# aprs_v2.net
KiCad netlist of a schematic drawn in EAGLE
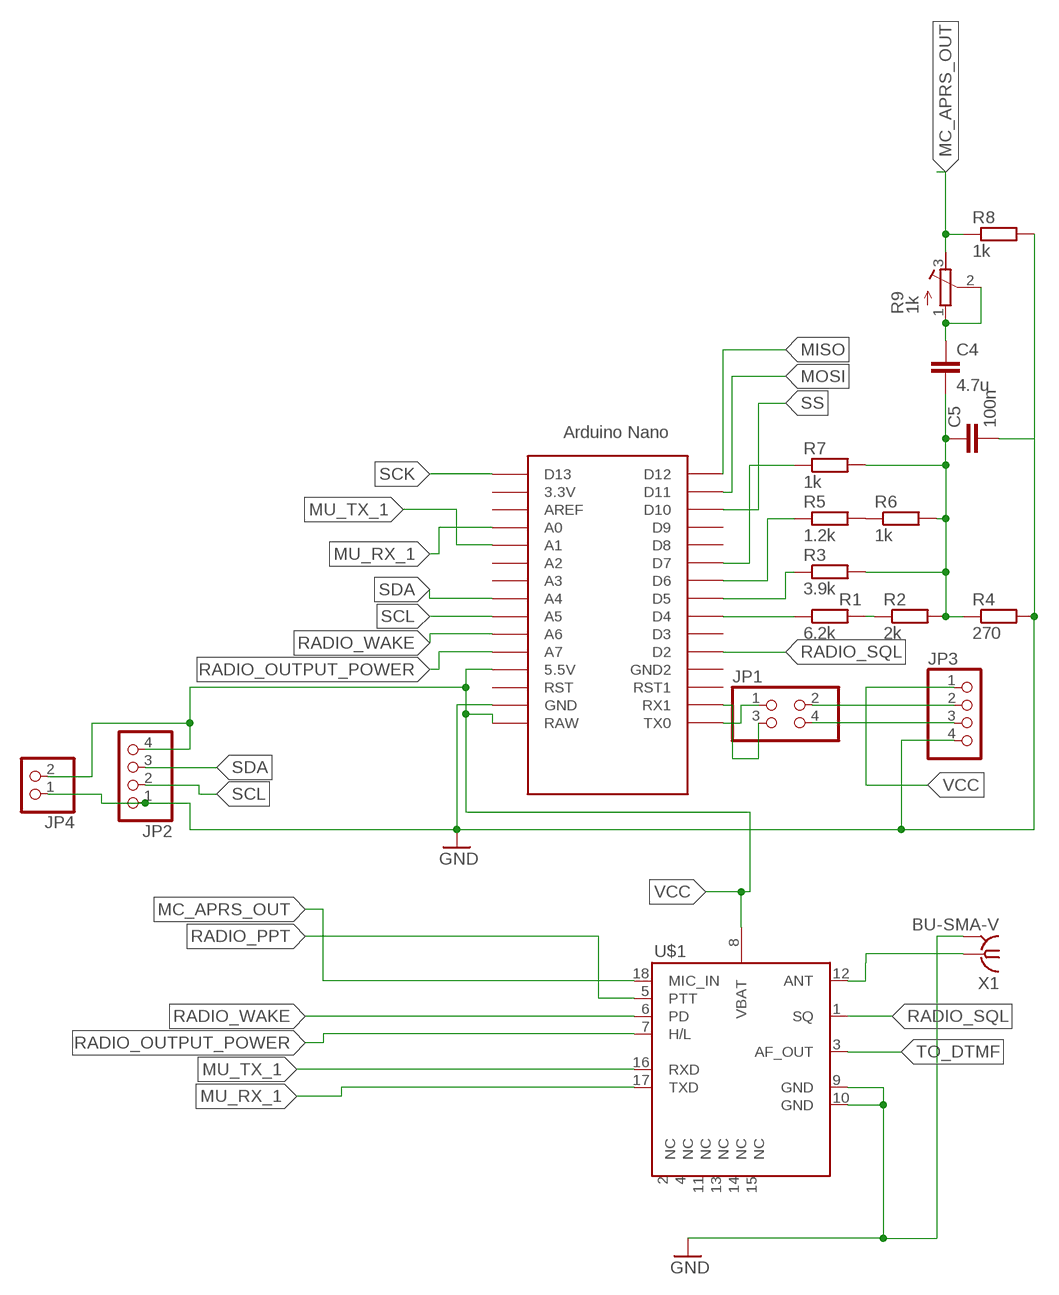
[diagram p0: schematic, sheet 1]

(export (version "E")
  (design (tool "Eeschema 10.0.6"))
  (components
    (comp (ref "C4")
      (value "4.7u")
      (footprint "eagle-import:C1206")
      (libsource (lib "eagle-import") (part "C-EUC1206"))
    )
    (comp (ref "C5")
      (value "100n")
      (footprint "eagle-import:C0805")
      (libsource (lib "eagle-import") (part "C-EUC0805"))
    )
    (comp (ref "JP1")
      (value "PINHD-2X2")
      (footprint "eagle-import:2X02")
      (libsource (lib "eagle-import") (part "PINHD-2X2"))
    )
    (comp (ref "JP2")
      (value "PINHD-1X4")
      (footprint "eagle-import:1X04")
      (libsource (lib "eagle-import") (part "PINHD-1X4"))
    )
    (comp (ref "JP3")
      (value "PINHD-1X4")
      (footprint "eagle-import:1X04")
      (libsource (lib "eagle-import") (part "PINHD-1X4"))
    )
    (comp (ref "JP4")
      (value "PINHD-1X2")
      (footprint "eagle-import:1X02")
      (libsource (lib "eagle-import") (part "PINHD-1X2"))
    )
    (comp (ref "R1")
      (value "6.2k")
      (footprint "eagle-import:0207_7")
      (libsource (lib "eagle-import") (part "R-EU_0207/7"))
    )
    (comp (ref "R2")
      (value "2k")
      (footprint "eagle-import:0207_7")
      (libsource (lib "eagle-import") (part "R-EU_0207/7"))
    )
    (comp (ref "R3")
      (value "3.9k")
      (footprint "eagle-import:0207_7")
      (libsource (lib "eagle-import") (part "R-EU_0207/7"))
    )
    (comp (ref "R4")
      (value "270")
      (footprint "eagle-import:0204_7")
      (libsource (lib "eagle-import") (part "R-EU_0204/7"))
    )
    (comp (ref "R5")
      (value "1.2k")
      (footprint "eagle-import:0207_7")
      (libsource (lib "eagle-import") (part "R-EU_0207/7"))
    )
    (comp (ref "R6")
      (value "1k")
      (footprint "eagle-import:0207_7")
      (libsource (lib "eagle-import") (part "R-EU_0207/7"))
    )
    (comp (ref "R7")
      (value "1k")
      (footprint "eagle-import:0204_5")
      (libsource (lib "eagle-import") (part "R-EU_0204/5"))
    )
    (comp (ref "R8")
      (value "1k")
      (footprint "eagle-import:0207_12")
      (libsource (lib "eagle-import") (part "R-EU_0207/12"))
    )
    (comp (ref "R9")
      (value "1k")
      (footprint "eagle-import:RTRIM3339P")
      (libsource (lib "eagle-import") (part "R-TRIMM3339P"))
    )
    (comp (ref "U$1")
      (value "DRA818A")
      (footprint "eagle-import:DRA818A")
      (libsource (lib "eagle-import") (part "DRA818A"))
    )
    (comp (ref "U$2")
      (value "NANO")
      (footprint "eagle-import:NANO")
      (libsource (lib "eagle-import") (part "NANO"))
    )
    (comp (ref "X1")
      (value "BU-SMA-V")
      (footprint "eagle-import:BU-SMA-V")
      (libsource (lib "eagle-import") (part "BU-SMA-V"))
    )
  )
  (nets
    (net (code "1") (name "GND") (class "Default")
      (node (ref "C5") (pin "2") (pinfunction "2_2") (pintype "passive"))
      (node (ref "JP2") (pin "1") (pinfunction "1_1") (pintype "passive"))
      (node (ref "JP3") (pin "4") (pinfunction "4_4") (pintype "passive"))
      (node (ref "JP4") (pin "1") (pinfunction "1_1") (pintype "passive"))
      (node (ref "R4") (pin "2") (pinfunction "2_2") (pintype "passive"))
      (node (ref "R8") (pin "2") (pinfunction "2_2") (pintype "passive"))
      (node (ref "U$1") (pin "10") (pinfunction "GND_10") (pintype "bidirectional"))
      (node (ref "U$1") (pin "9") (pinfunction "GND_9") (pintype "bidirectional"))
      (node (ref "U$2") (pin "GND") (pinfunction "GND_GND") (pintype "bidirectional"))
      (node (ref "X1") (pin "2") (pinfunction "2_2") (pintype "passive"))
      (node (ref "X1") (pin "3") (pinfunction "2_3") (pintype "passive"))
      (node (ref "X1") (pin "4") (pinfunction "2_4") (pintype "passive"))
      (node (ref "X1") (pin "5") (pinfunction "2_5") (pintype "passive"))
    )
    (net (code "2") (name "MC_APRS_OUT") (class "Default")
      (node (ref "R8") (pin "1") (pinfunction "1_1") (pintype "passive"))
      (node (ref "R9") (pin "3") (pinfunction "E_3") (pintype "passive"))
      (node (ref "U$1") (pin "18") (pinfunction "MIC_IN_18") (pintype "bidirectional"))
    )
    (net (code "3") (name "MISO") (class "Default")
      (node (ref "U$2") (pin "D12") (pinfunction "D12_D12") (pintype "bidirectional"))
    )
    (net (code "4") (name "MOSI") (class "Default")
      (node (ref "U$2") (pin "D11") (pinfunction "D11_D11") (pintype "bidirectional"))
    )
    (net (code "5") (name "MU_RX_1") (class "Default")
      (node (ref "U$1") (pin "17") (pinfunction "TXD_17") (pintype "bidirectional"))
      (node (ref "U$2") (pin "A0") (pinfunction "A0_A0") (pintype "bidirectional"))
    )
    (net (code "6") (name "MU_TX_1") (class "Default")
      (node (ref "U$1") (pin "16") (pinfunction "RXD_16") (pintype "bidirectional"))
      (node (ref "U$2") (pin "A1") (pinfunction "A1_A1") (pintype "bidirectional"))
    )
    (net (code "7") (name "Net-(C4-Pad2)") (class "Default")
      (node (ref "C4") (pin "2") (pinfunction "2_2") (pintype "passive"))
      (node (ref "C5") (pin "1") (pinfunction "1_1") (pintype "passive"))
      (node (ref "R2") (pin "2") (pinfunction "2_2") (pintype "passive"))
      (node (ref "R3") (pin "2") (pinfunction "2_2") (pintype "passive"))
      (node (ref "R4") (pin "1") (pinfunction "1_1") (pintype "passive"))
      (node (ref "R6") (pin "2") (pinfunction "2_2") (pintype "passive"))
      (node (ref "R7") (pin "2") (pinfunction "2_2") (pintype "passive"))
    )
    (net (code "8") (name "Net-(JP1-Pad1)") (class "Default")
      (node (ref "JP1") (pin "1") (pinfunction "1_1") (pintype "passive"))
      (node (ref "U$2") (pin "TX0") (pinfunction "TX0_TX0") (pintype "bidirectional"))
    )
    (net (code "9") (name "Net-(JP1-Pad2)") (class "Default")
      (node (ref "JP1") (pin "2") (pinfunction "2_2") (pintype "passive"))
      (node (ref "JP3") (pin "2") (pinfunction "2_2") (pintype "passive"))
    )
    (net (code "10") (name "Net-(JP1-Pad3)") (class "Default")
      (node (ref "JP1") (pin "3") (pinfunction "3_3") (pintype "passive"))
      (node (ref "U$2") (pin "RX1") (pinfunction "RX1_RX1") (pintype "bidirectional"))
    )
    (net (code "11") (name "Net-(JP1-Pad4)") (class "Default")
      (node (ref "JP1") (pin "4") (pinfunction "4_4") (pintype "passive"))
      (node (ref "JP3") (pin "3") (pinfunction "3_3") (pintype "passive"))
    )
    (net (code "12") (name "Net-(R1-Pad1)") (class "Default")
      (node (ref "R1") (pin "1") (pinfunction "1_1") (pintype "passive"))
      (node (ref "U$2") (pin "D4") (pinfunction "D4_D4") (pintype "bidirectional"))
    )
    (net (code "13") (name "Net-(R1-Pad2)") (class "Default")
      (node (ref "R1") (pin "2") (pinfunction "2_2") (pintype "passive"))
      (node (ref "R2") (pin "1") (pinfunction "1_1") (pintype "passive"))
    )
    (net (code "14") (name "Net-(R3-Pad1)") (class "Default")
      (node (ref "R3") (pin "1") (pinfunction "1_1") (pintype "passive"))
      (node (ref "U$2") (pin "D5") (pinfunction "D5_D5") (pintype "bidirectional"))
    )
    (net (code "15") (name "Net-(R5-Pad1)") (class "Default")
      (node (ref "R5") (pin "1") (pinfunction "1_1") (pintype "passive"))
      (node (ref "U$2") (pin "D6") (pinfunction "D6_D6") (pintype "bidirectional"))
    )
    (net (code "16") (name "Net-(R5-Pad2)") (class "Default")
      (node (ref "R5") (pin "2") (pinfunction "2_2") (pintype "passive"))
      (node (ref "R6") (pin "1") (pinfunction "1_1") (pintype "passive"))
    )
    (net (code "17") (name "Net-(R7-Pad1)") (class "Default")
      (node (ref "R7") (pin "1") (pinfunction "1_1") (pintype "passive"))
      (node (ref "U$2") (pin "D7") (pinfunction "D7_D7") (pintype "bidirectional"))
    )
    (net (code "18") (name "Net-(R9-A)") (class "Default")
      (node (ref "C4") (pin "1") (pinfunction "1_1") (pintype "passive"))
      (node (ref "R9") (pin "1") (pinfunction "A_1") (pintype "passive"))
      (node (ref "R9") (pin "2") (pinfunction "S_2") (pintype "passive"))
    )
    (net (code "19") (name "Net-(U$1-ANT)") (class "Default")
      (node (ref "U$1") (pin "12") (pinfunction "ANT_12") (pintype "bidirectional"))
      (node (ref "X1") (pin "1") (pinfunction "1_1") (pintype "passive"))
    )
    (net (code "20") (name "RADIO_OUTPUT_POWER") (class "Default")
      (node (ref "U$1") (pin "7") (pinfunction "H/L_7") (pintype "bidirectional"))
      (node (ref "U$2") (pin "A7") (pinfunction "A7_A7") (pintype "bidirectional"))
    )
    (net (code "21") (name "RADIO_PPT") (class "Default")
      (node (ref "U$1") (pin "5") (pinfunction "PTT_5") (pintype "bidirectional"))
    )
    (net (code "22") (name "RADIO_SQL") (class "Default")
      (node (ref "U$1") (pin "1") (pinfunction "SQ_1") (pintype "bidirectional"))
      (node (ref "U$2") (pin "D2") (pinfunction "D2_D2") (pintype "bidirectional"))
    )
    (net (code "23") (name "RADIO_WAKE") (class "Default")
      (node (ref "U$1") (pin "6") (pinfunction "PD_6") (pintype "bidirectional"))
      (node (ref "U$2") (pin "A6") (pinfunction "A6_A6") (pintype "bidirectional"))
    )
    (net (code "24") (name "SCK") (class "Default")
      (node (ref "U$2") (pin "D13") (pinfunction "D13_D13") (pintype "bidirectional"))
    )
    (net (code "25") (name "SCL") (class "Default")
      (node (ref "JP2") (pin "2") (pinfunction "2_2") (pintype "passive"))
      (node (ref "U$2") (pin "A5") (pinfunction "A5_A5") (pintype "bidirectional"))
    )
    (net (code "26") (name "SDA") (class "Default")
      (node (ref "JP2") (pin "3") (pinfunction "3_3") (pintype "passive"))
      (node (ref "U$2") (pin "A4") (pinfunction "A4_A4") (pintype "bidirectional"))
    )
    (net (code "27") (name "SS") (class "Default")
      (node (ref "U$2") (pin "D10") (pinfunction "D10_D10") (pintype "bidirectional"))
    )
    (net (code "28") (name "TO_DTMF") (class "Default")
      (node (ref "U$1") (pin "3") (pinfunction "AF_OUT_3") (pintype "bidirectional"))
    )
    (net (code "29") (name "VCC") (class "Default")
      (node (ref "JP2") (pin "4") (pinfunction "4_4") (pintype "passive"))
      (node (ref "JP3") (pin "1") (pinfunction "1_1") (pintype "passive"))
      (node (ref "JP4") (pin "2") (pinfunction "2_2") (pintype "passive"))
      (node (ref "U$1") (pin "8") (pinfunction "VBAT_8") (pintype "bidirectional"))
      (node (ref "U$2") (pin "5V") (pinfunction "5.5V_5V") (pintype "bidirectional"))
      (node (ref "U$2") (pin "RAW") (pinfunction "RAW_RAW") (pintype "bidirectional"))
    )
    (net (code "30") (name "unconnected-(U$1-NC-Pad2)") (class "Default")
      (node (ref "U$1") (pin "2") (pinfunction "NC_2") (pintype "bidirectional"))
    )
    (net (code "31") (name "unconnected-(U$1-NC-Pad4)") (class "Default")
      (node (ref "U$1") (pin "4") (pinfunction "NC_4") (pintype "bidirectional"))
    )
    (net (code "32") (name "unconnected-(U$1-NC-Pad11)") (class "Default")
      (node (ref "U$1") (pin "11") (pinfunction "NC_11") (pintype "bidirectional"))
    )
    (net (code "33") (name "unconnected-(U$1-NC-Pad13)") (class "Default")
      (node (ref "U$1") (pin "13") (pinfunction "NC_13") (pintype "bidirectional"))
    )
    (net (code "34") (name "unconnected-(U$1-NC-Pad14)") (class "Default")
      (node (ref "U$1") (pin "14") (pinfunction "NC_14") (pintype "bidirectional"))
    )
    (net (code "35") (name "unconnected-(U$1-NC-Pad15)") (class "Default")
      (node (ref "U$1") (pin "15") (pinfunction "NC_15") (pintype "bidirectional"))
    )
    (net (code "36") (name "unconnected-(U$2-GND2-PadGND1)") (class "Default")
      (node (ref "U$2") (pin "GND1") (pinfunction "GND2_GND1") (pintype "bidirectional"))
    )
    (net (code "37") (name "unconnected-(U$2-Pad3.3V)") (class "Default")
      (node (ref "U$2") (pin "3.3V") (pinfunction "3.3V_3.3V") (pintype "bidirectional"))
    )
    (net (code "38") (name "unconnected-(U$2-PadA2)") (class "Default")
      (node (ref "U$2") (pin "A2") (pinfunction "A2_A2") (pintype "bidirectional"))
    )
    (net (code "39") (name "unconnected-(U$2-PadA3)") (class "Default")
      (node (ref "U$2") (pin "A3") (pinfunction "A3_A3") (pintype "bidirectional"))
    )
    (net (code "40") (name "unconnected-(U$2-PadAREF)") (class "Default")
      (node (ref "U$2") (pin "AREF") (pinfunction "AREF_AREF") (pintype "bidirectional"))
    )
    (net (code "41") (name "unconnected-(U$2-PadD3)") (class "Default")
      (node (ref "U$2") (pin "D3") (pinfunction "D3_D3") (pintype "bidirectional"))
    )
    (net (code "42") (name "unconnected-(U$2-PadD8)") (class "Default")
      (node (ref "U$2") (pin "D8") (pinfunction "D8_D8") (pintype "bidirectional"))
    )
    (net (code "43") (name "unconnected-(U$2-PadD9)") (class "Default")
      (node (ref "U$2") (pin "D9") (pinfunction "D9_D9") (pintype "bidirectional"))
    )
    (net (code "44") (name "unconnected-(U$2-PadICSP1)") (class "Default")
      (node (ref "U$2") (pin "ICSP1") (pinfunction "ICSP1_ICSP1") (pintype "bidirectional"))
    )
    (net (code "45") (name "unconnected-(U$2-PadICSP2)") (class "Default")
      (node (ref "U$2") (pin "ICSP2") (pinfunction "ICSP2_ICSP2") (pintype "bidirectional"))
    )
    (net (code "46") (name "unconnected-(U$2-PadICSP3)") (class "Default")
      (node (ref "U$2") (pin "ICSP3") (pinfunction "ICSP3_ICSP3") (pintype "bidirectional"))
    )
    (net (code "47") (name "unconnected-(U$2-PadICSP4)") (class "Default")
      (node (ref "U$2") (pin "ICSP4") (pinfunction "ICSP4_ICSP4") (pintype "bidirectional"))
    )
    (net (code "48") (name "unconnected-(U$2-PadICSP5)") (class "Default")
      (node (ref "U$2") (pin "ICSP5") (pinfunction "ICSP5_ICSP5") (pintype "bidirectional"))
    )
    (net (code "49") (name "unconnected-(U$2-PadICSP6)") (class "Default")
      (node (ref "U$2") (pin "ICSP6") (pinfunction "ICSP6_ICSP6") (pintype "bidirectional"))
    )
    (net (code "50") (name "unconnected-(U$2-PadRST)") (class "Default")
      (node (ref "U$2") (pin "RST") (pinfunction "RST_RST") (pintype "bidirectional"))
    )
    (net (code "51") (name "unconnected-(U$2-PadRST1)") (class "Default")
      (node (ref "U$2") (pin "RST1") (pinfunction "RST1_RST1") (pintype "bidirectional"))
    )
  )
)
